# 6moduleboard.net
KiCad netlist of a schematic drawn in EAGLE
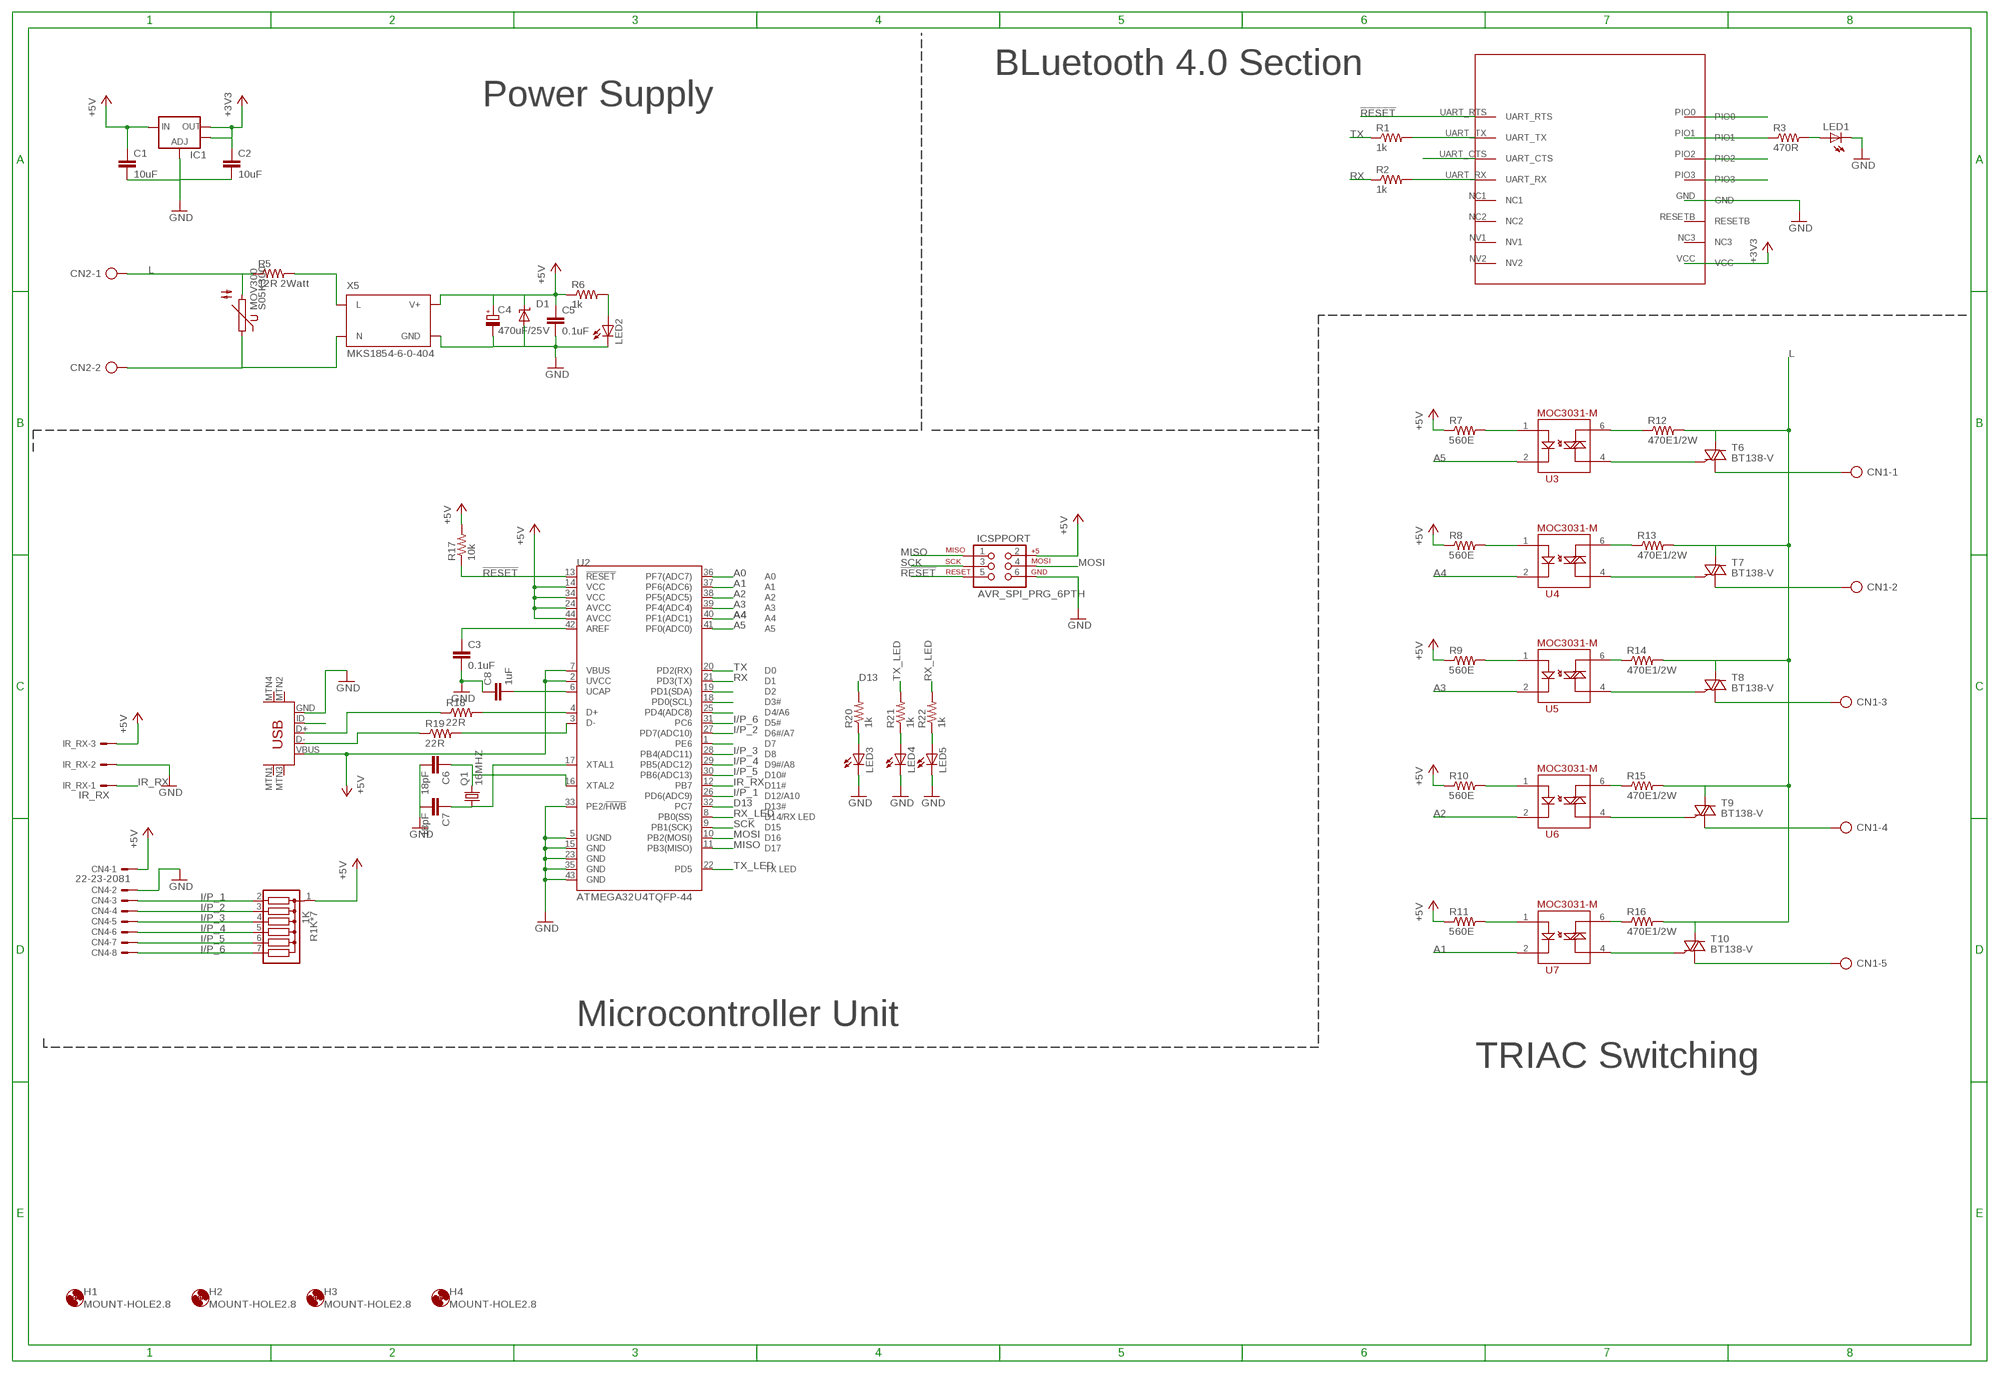
[diagram p0: schematic, sheet 1]

(export (version "E")
  (design (tool "Eeschema 10.0.6"))
  (components
    (comp (ref "C1")
      (value "10uF")
      (footprint "eagle-import:1206")
      (libsource (lib "eagle-import") (part "10UF-6.3V-20%(1206)"))
    )
    (comp (ref "C2")
      (value "10uF")
      (footprint "eagle-import:1206")
      (libsource (lib "eagle-import") (part "10UF-6.3V-20%(1206)"))
    )
    (comp (ref "C3")
      (value "0.1uF")
      (footprint "eagle-import:1206")
      (libsource (lib "eagle-import") (part "CAP1206"))
    )
    (comp (ref "C4")
      (value "470uF/25V")
      (footprint "eagle-import:E5-8,5")
      (libsource (lib "eagle-import") (part "CPOL-EUE5-8.5"))
    )
    (comp (ref "C5")
      (value "0.1uF")
      (footprint "eagle-import:1206")
      (libsource (lib "eagle-import") (part "1.0UF50V10%(1206)"))
    )
    (comp (ref "C6")
      (value "18pF")
      (footprint "eagle-import:1206")
      (libsource (lib "eagle-import") (part "CAP1206"))
    )
    (comp (ref "C7")
      (value "18pF")
      (footprint "eagle-import:1206")
      (libsource (lib "eagle-import") (part "CAP1206"))
    )
    (comp (ref "C8")
      (value "1uF")
      (footprint "eagle-import:1206")
      (libsource (lib "eagle-import") (part "CAP1206"))
    )
    (comp (ref "CN1")
      (value "AK300/5")
      (footprint "eagle-import:AK300_5")
      (libsource (lib "eagle-import") (part "AK300/5"))
    )
    (comp (ref "CN2")
      (value "AK300/2")
      (footprint "eagle-import:AK300_2")
      (libsource (lib "eagle-import") (part "AK300/2"))
    )
    (comp (ref "CN4")
      (value "22-23-2081")
      (footprint "eagle-import:22-23-2081")
      (fields (field (name "MF") "MOLEX"))
      (libsource (lib "eagle-import") (part "22-23-2081"))
    )
    (comp (ref "D1")
      (value "SUPPRESSOR-SMBJ")
      (footprint "eagle-import:SMBJ")
      (libsource (lib "eagle-import") (part "SUPPRESSOR-SMBJ"))
    )
    (comp (ref "H1")
      (value "MOUNT-HOLE2.8")
      (footprint "eagle-import:2,8")
      (libsource (lib "eagle-import") (part "MOUNT-HOLE2.8"))
    )
    (comp (ref "H2")
      (value "MOUNT-HOLE2.8")
      (footprint "eagle-import:2,8")
      (libsource (lib "eagle-import") (part "MOUNT-HOLE2.8"))
    )
    (comp (ref "H3")
      (value "MOUNT-HOLE2.8")
      (footprint "eagle-import:2,8")
      (libsource (lib "eagle-import") (part "MOUNT-HOLE2.8"))
    )
    (comp (ref "H4")
      (value "MOUNT-HOLE2.8")
      (footprint "eagle-import:2,8")
      (libsource (lib "eagle-import") (part "MOUNT-HOLE2.8"))
    )
    (comp (ref "IC1")
      (value "V_REG_LM1117SOT223")
      (footprint "eagle-import:SOT223")
      (libsource (lib "eagle-import") (part "V_REG_LM1117SOT223"))
    )
    (comp (ref "ICSPPORT")
      (value "AVR_SPI_PRG_6PTH")
      (footprint "eagle-import:2X3")
      (libsource (lib "eagle-import") (part "AVR_SPI_PRG_6PTH"))
    )
    (comp (ref "IR_RX")
      (value "IR_RX")
      (footprint "eagle-import:22-23-2031")
      (fields (field (name "MF") "MOLEX") (field (name "MPN") "22-23-2031"))
      (libsource (lib "eagle-import") (part "22-23-2031"))
    )
    (comp (ref "LED1")
      (value "LEDSMT1206")
      (footprint "eagle-import:1206")
      (libsource (lib "eagle-import") (part "LEDSMT1206"))
    )
    (comp (ref "LED2")
      (value "LEDSMT1206")
      (footprint "eagle-import:1206")
      (libsource (lib "eagle-import") (part "LEDSMT1206"))
    )
    (comp (ref "LED3")
      (value "LEDSMT1206")
      (footprint "eagle-import:1206")
      (libsource (lib "eagle-import") (part "LEDSMT1206"))
    )
    (comp (ref "LED4")
      (value "LEDSMT1206")
      (footprint "eagle-import:1206")
      (libsource (lib "eagle-import") (part "LEDSMT1206"))
    )
    (comp (ref "LED5")
      (value "LEDSMT1206")
      (footprint "eagle-import:1206")
      (libsource (lib "eagle-import") (part "LEDSMT1206"))
    )
    (comp (ref "MOV300")
      (value "S05K300")
      (footprint "eagle-import:S05K300")
      (libsource (lib "eagle-import") (part "S05K300"))
    )
    (comp (ref "Q1")
      (value "16MHZ")
      (footprint "eagle-import:HC49UP")
      (libsource (lib "eagle-import") (part "CRYSTALHC49UP"))
    )
    (comp (ref "R1")
      (value "1k")
      (footprint "eagle-import:1206")
      (libsource (lib "eagle-import") (part "RESISTOR1206"))
    )
    (comp (ref "R1K*7")
      (value "1K")
      (footprint "eagle-import:SIL7")
      (libsource (lib "eagle-import") (part "G06R"))
    )
    (comp (ref "R2")
      (value "1k")
      (footprint "eagle-import:1206")
      (libsource (lib "eagle-import") (part "RESISTOR1206"))
    )
    (comp (ref "R3")
      (value "470R")
      (footprint "eagle-import:1206")
      (libsource (lib "eagle-import") (part "RESISTOR1206"))
    )
    (comp (ref "R5")
      (value "12R 2Watt")
      (footprint "eagle-import:0207_10")
      (libsource (lib "eagle-import") (part "R-US_0207/10"))
    )
    (comp (ref "R6")
      (value "1k")
      (footprint "eagle-import:1206")
      (libsource (lib "eagle-import") (part "RESISTOR1206"))
    )
    (comp (ref "R7")
      (value "560E")
      (footprint "eagle-import:1206")
      (libsource (lib "eagle-import") (part "SparkFun-Resistors_RESISTOR1206"))
    )
    (comp (ref "R8")
      (value "560E")
      (footprint "eagle-import:1206")
      (libsource (lib "eagle-import") (part "SparkFun-Resistors_RESISTOR1206"))
    )
    (comp (ref "R9")
      (value "560E")
      (footprint "eagle-import:1206")
      (libsource (lib "eagle-import") (part "SparkFun-Resistors_RESISTOR1206"))
    )
    (comp (ref "R10")
      (value "560E")
      (footprint "eagle-import:1206")
      (libsource (lib "eagle-import") (part "SparkFun-Resistors_RESISTOR1206"))
    )
    (comp (ref "R11")
      (value "560E")
      (footprint "eagle-import:1206")
      (libsource (lib "eagle-import") (part "SparkFun-Resistors_RESISTOR1206"))
    )
    (comp (ref "R12")
      (value "470E1/2W")
      (footprint "eagle-import:0411V")
      (libsource (lib "eagle-import") (part "R-US_0411/3V"))
    )
    (comp (ref "R13")
      (value "470E1/2W")
      (footprint "eagle-import:0411V")
      (libsource (lib "eagle-import") (part "R-US_0411/3V"))
    )
    (comp (ref "R14")
      (value "470E1/2W")
      (footprint "eagle-import:0411V")
      (libsource (lib "eagle-import") (part "R-US_0411/3V"))
    )
    (comp (ref "R15")
      (value "470E1/2W")
      (footprint "eagle-import:0411V")
      (libsource (lib "eagle-import") (part "R-US_0411/3V"))
    )
    (comp (ref "R16")
      (value "470E1/2W")
      (footprint "eagle-import:0411V")
      (libsource (lib "eagle-import") (part "R-US_0411/3V"))
    )
    (comp (ref "R17")
      (value "10k")
      (footprint "eagle-import:1206")
      (libsource (lib "eagle-import") (part "RESISTOR1206"))
    )
    (comp (ref "R18")
      (value "22R")
      (footprint "eagle-import:1206")
      (libsource (lib "eagle-import") (part "RESISTOR1206"))
    )
    (comp (ref "R19")
      (value "22R")
      (footprint "eagle-import:1206")
      (libsource (lib "eagle-import") (part "RESISTOR1206"))
    )
    (comp (ref "R20")
      (value "1k")
      (footprint "eagle-import:1206")
      (libsource (lib "eagle-import") (part "RESISTOR1206"))
    )
    (comp (ref "R21")
      (value "1k")
      (footprint "eagle-import:1206")
      (libsource (lib "eagle-import") (part "RESISTOR1206"))
    )
    (comp (ref "R22")
      (value "1k")
      (footprint "eagle-import:1206")
      (libsource (lib "eagle-import") (part "RESISTOR1206"))
    )
    (comp (ref "T6")
      (value "BT138-V")
      (footprint "eagle-import:TO220BV")
      (libsource (lib "eagle-import") (part "BT138-V"))
    )
    (comp (ref "T7")
      (value "BT138-V")
      (footprint "eagle-import:TO220BV")
      (libsource (lib "eagle-import") (part "BT138-V"))
    )
    (comp (ref "T8")
      (value "BT138-V")
      (footprint "eagle-import:TO220BV")
      (libsource (lib "eagle-import") (part "BT138-V"))
    )
    (comp (ref "T9")
      (value "BT138-V")
      (footprint "eagle-import:TO220BV")
      (libsource (lib "eagle-import") (part "BT138-V"))
    )
    (comp (ref "T10")
      (value "BT138-V")
      (footprint "eagle-import:TO220BV")
      (libsource (lib "eagle-import") (part "BT138-V"))
    )
    (comp (ref "U$1")
      (value "HM-11")
      (footprint "eagle-import:HM-11")
      (libsource (lib "eagle-import") (part "HM-11"))
    )
    (comp (ref "U2")
      (value "ATMEGA32U4TQFP-44")
      (footprint "eagle-import:TQFP44")
      (libsource (lib "eagle-import") (part "ATMEGA32U4TQFP-44"))
    )
    (comp (ref "U3")
      (value "MOC3083")
      (footprint "eagle-import:DIL06")
      (libsource (lib "eagle-import") (part "MOC3031-M"))
    )
    (comp (ref "U4")
      (value "MOC3083")
      (footprint "eagle-import:DIL06")
      (libsource (lib "eagle-import") (part "MOC3031-M"))
    )
    (comp (ref "U5")
      (value "MOC3083")
      (footprint "eagle-import:DIL06")
      (libsource (lib "eagle-import") (part "MOC3031-M"))
    )
    (comp (ref "U6")
      (value "MOC3083")
      (footprint "eagle-import:DIL06")
      (libsource (lib "eagle-import") (part "MOC3031-M"))
    )
    (comp (ref "U7")
      (value "MOC3083")
      (footprint "eagle-import:DIL06")
      (libsource (lib "eagle-import") (part "MOC3031-M"))
    )
    (comp (ref "U8")
      (value "USB-MINIB-5PIN")
      (footprint "eagle-import:USB-MINIB")
      (libsource (lib "eagle-import") (part "USB-MINIB-5PIN"))
    )
    (comp (ref "X5")
      (value "MKS1854-6-0-404")
      (footprint "eagle-import:MKS1854-6-0-404")
      (libsource (lib "eagle-import") (part "MKS1854-6-0-404"))
    )
  )
  (nets
    (net (code "1") (name "+3V3") (class "Default")
      (node (ref "C2") (pin "1") (pinfunction "1_1") (pintype "passive"))
      (node (ref "IC1") (pin "2") (pinfunction "OUT_2") (pintype "output"))
      (node (ref "IC1") (pin "4") (pinfunction "OUT_4") (pintype "output"))
      (node (ref "U$1") (pin "VCC") (pinfunction "VCC_VCC") (pintype "bidirectional"))
    )
    (net (code "2") (name "+5V") (class "Default")
      (node (ref "C1") (pin "1") (pinfunction "1_1") (pintype "passive"))
      (node (ref "C4") (pin "+") (pinfunction "+_+") (pintype "passive"))
      (node (ref "C5") (pin "1") (pinfunction "1_1") (pintype "passive"))
      (node (ref "CN4") (pin "1") (pinfunction "S_1") (pintype "passive"))
      (node (ref "D1") (pin "C") (pinfunction "C_C") (pintype "passive"))
      (node (ref "IC1") (pin "3") (pinfunction "IN_3") (pintype "input"))
      (node (ref "ICSPPORT") (pin "2") (pinfunction "2_2") (pintype "passive"))
      (node (ref "IR_RX") (pin "3") (pinfunction "S_3") (pintype "passive"))
      (node (ref "R10") (pin "1") (pinfunction "1_1") (pintype "passive"))
      (node (ref "R11") (pin "1") (pinfunction "1_1") (pintype "passive"))
      (node (ref "R17") (pin "2") (pinfunction "2_2") (pintype "passive"))
      (node (ref "R1K*7") (pin "1") (pinfunction "1_1") (pintype "passive"))
      (node (ref "R6") (pin "1") (pinfunction "1_1") (pintype "passive"))
      (node (ref "R7") (pin "1") (pinfunction "1_1") (pintype "passive"))
      (node (ref "R8") (pin "1") (pinfunction "1_1") (pintype "passive"))
      (node (ref "R9") (pin "1") (pinfunction "1_1") (pintype "passive"))
      (node (ref "U2") (pin "14") (pinfunction "VCC_14") (pintype "bidirectional"))
      (node (ref "U2") (pin "2") (pinfunction "UVCC_2") (pintype "bidirectional"))
      (node (ref "U2") (pin "24") (pinfunction "AVCC_24") (pintype "bidirectional"))
      (node (ref "U2") (pin "34") (pinfunction "VCC_34") (pintype "bidirectional"))
      (node (ref "U2") (pin "44") (pinfunction "AVCC_44") (pintype "bidirectional"))
      (node (ref "U2") (pin "7") (pinfunction "VBUS_7") (pintype "bidirectional"))
      (node (ref "U8") (pin "VBUS") (pinfunction "VBUS_VBUS") (pintype "bidirectional"))
      (node (ref "X5") (pin "3") (pinfunction "V+_3") (pintype "input"))
    )
    (net (code "3") (name "/A0") (class "Default")
      (node (ref "U2") (pin "36") (pinfunction "PF7(ADC7)_36") (pintype "bidirectional"))
    )
    (net (code "4") (name "/A1") (class "Default")
      (node (ref "U2") (pin "37") (pinfunction "PF6(ADC6)_37") (pintype "bidirectional"))
      (node (ref "U7") (pin "2") (pinfunction "2_2") (pintype "bidirectional"))
    )
    (net (code "5") (name "/A2") (class "Default")
      (node (ref "U2") (pin "38") (pinfunction "PF5(ADC5)_38") (pintype "bidirectional"))
      (node (ref "U6") (pin "2") (pinfunction "2_2") (pintype "bidirectional"))
    )
    (net (code "6") (name "/A3") (class "Default")
      (node (ref "U2") (pin "39") (pinfunction "PF4(ADC4)_39") (pintype "bidirectional"))
      (node (ref "U5") (pin "2") (pinfunction "2_2") (pintype "bidirectional"))
    )
    (net (code "7") (name "/A4") (class "Default")
      (node (ref "U2") (pin "40") (pinfunction "PF1(ADC1)_40") (pintype "bidirectional"))
      (node (ref "U4") (pin "2") (pinfunction "2_2") (pintype "bidirectional"))
    )
    (net (code "8") (name "/A5") (class "Default")
      (node (ref "U2") (pin "41") (pinfunction "PF0(ADC0)_41") (pintype "bidirectional"))
      (node (ref "U3") (pin "2") (pinfunction "2_2") (pintype "bidirectional"))
    )
    (net (code "9") (name "/D13") (class "Default")
      (node (ref "R20") (pin "2") (pinfunction "2_2") (pintype "passive"))
      (node (ref "U2") (pin "32") (pinfunction "PC7_32") (pintype "bidirectional"))
    )
    (net (code "10") (name "/IR_RX") (class "Default")
      (node (ref "IR_RX") (pin "1") (pinfunction "S_1") (pintype "passive"))
      (node (ref "U2") (pin "12") (pinfunction "PB7_12") (pintype "bidirectional"))
    )
    (net (code "11") (name "/I{slash}P_1") (class "Default")
      (node (ref "CN4") (pin "3") (pinfunction "S_3") (pintype "passive"))
      (node (ref "R1K*7") (pin "2") (pinfunction "2_2") (pintype "passive"))
      (node (ref "U2") (pin "26") (pinfunction "PD6(ADC9)_26") (pintype "bidirectional"))
    )
    (net (code "12") (name "/I{slash}P_2") (class "Default")
      (node (ref "CN4") (pin "4") (pinfunction "S_4") (pintype "passive"))
      (node (ref "R1K*7") (pin "3") (pinfunction "3_3") (pintype "passive"))
      (node (ref "U2") (pin "27") (pinfunction "PD7(ADC10)_27") (pintype "bidirectional"))
    )
    (net (code "13") (name "/I{slash}P_3") (class "Default")
      (node (ref "CN4") (pin "5") (pinfunction "S_5") (pintype "passive"))
      (node (ref "R1K*7") (pin "4") (pinfunction "4_4") (pintype "passive"))
      (node (ref "U2") (pin "28") (pinfunction "PB4(ADC11)_28") (pintype "bidirectional"))
    )
    (net (code "14") (name "/I{slash}P_4") (class "Default")
      (node (ref "CN4") (pin "6") (pinfunction "S_6") (pintype "passive"))
      (node (ref "R1K*7") (pin "5") (pinfunction "5_5") (pintype "passive"))
      (node (ref "U2") (pin "29") (pinfunction "PB5(ADC12)_29") (pintype "bidirectional"))
    )
    (net (code "15") (name "/I{slash}P_5") (class "Default")
      (node (ref "CN4") (pin "7") (pinfunction "S_7") (pintype "passive"))
      (node (ref "R1K*7") (pin "6") (pinfunction "6_6") (pintype "passive"))
      (node (ref "U2") (pin "30") (pinfunction "PB6(ADC13)_30") (pintype "bidirectional"))
    )
    (net (code "16") (name "/I{slash}P_6") (class "Default")
      (node (ref "CN4") (pin "8") (pinfunction "S_8") (pintype "passive"))
      (node (ref "R1K*7") (pin "7") (pinfunction "7_7") (pintype "passive"))
      (node (ref "U2") (pin "31") (pinfunction "PC6_31") (pintype "bidirectional"))
    )
    (net (code "17") (name "/L") (class "Default")
      (node (ref "CN2") (pin "1") (pinfunction "KL_1") (pintype "passive"))
      (node (ref "MOV300") (pin "2") (pinfunction "2_2") (pintype "passive"))
      (node (ref "R12") (pin "2") (pinfunction "2_2") (pintype "passive"))
      (node (ref "R13") (pin "2") (pinfunction "2_2") (pintype "passive"))
      (node (ref "R14") (pin "2") (pinfunction "2_2") (pintype "passive"))
      (node (ref "R15") (pin "2") (pinfunction "2_2") (pintype "passive"))
      (node (ref "R16") (pin "2") (pinfunction "2_2") (pintype "passive"))
      (node (ref "R5") (pin "1") (pinfunction "1_1") (pintype "passive"))
      (node (ref "T10") (pin "T2") (pinfunction "A2_T2") (pintype "passive"))
      (node (ref "T6") (pin "T2") (pinfunction "A2_T2") (pintype "passive"))
      (node (ref "T7") (pin "T2") (pinfunction "A2_T2") (pintype "passive"))
      (node (ref "T8") (pin "T2") (pinfunction "A2_T2") (pintype "passive"))
      (node (ref "T9") (pin "T2") (pinfunction "A2_T2") (pintype "passive"))
    )
    (net (code "18") (name "/MISO") (class "Default")
      (node (ref "ICSPPORT") (pin "1") (pinfunction "1_1") (pintype "passive"))
      (node (ref "U2") (pin "11") (pinfunction "PB3(MISO)_11") (pintype "bidirectional"))
    )
    (net (code "19") (name "/MOSI") (class "Default")
      (node (ref "ICSPPORT") (pin "4") (pinfunction "4_4") (pintype "passive"))
      (node (ref "U2") (pin "10") (pinfunction "PB2(MOSI)_10") (pintype "bidirectional"))
    )
    (net (code "20") (name "/RX") (class "Default")
      (node (ref "R2") (pin "1") (pinfunction "1_1") (pintype "passive"))
      (node (ref "U2") (pin "21") (pinfunction "PD3(TX)_21") (pintype "bidirectional"))
    )
    (net (code "21") (name "/RX_LED") (class "Default")
      (node (ref "R22") (pin "2") (pinfunction "2_2") (pintype "passive"))
      (node (ref "U2") (pin "8") (pinfunction "PB0(SS)_8") (pintype "bidirectional"))
    )
    (net (code "22") (name "/SCK") (class "Default")
      (node (ref "ICSPPORT") (pin "3") (pinfunction "3_3") (pintype "passive"))
      (node (ref "U2") (pin "9") (pinfunction "PB1(SCK)_9") (pintype "bidirectional"))
    )
    (net (code "23") (name "/TX") (class "Default")
      (node (ref "R1") (pin "1") (pinfunction "1_1") (pintype "passive"))
      (node (ref "U2") (pin "20") (pinfunction "PD2(RX)_20") (pintype "bidirectional"))
    )
    (net (code "24") (name "/TX_LED") (class "Default")
      (node (ref "R21") (pin "2") (pinfunction "2_2") (pintype "passive"))
      (node (ref "U2") (pin "22") (pinfunction "PD5_22") (pintype "bidirectional"))
    )
    (net (code "25") (name "/~{RESET}") (class "Default")
      (node (ref "ICSPPORT") (pin "5") (pinfunction "5_5") (pintype "passive"))
      (node (ref "R17") (pin "1") (pinfunction "1_1") (pintype "passive"))
      (node (ref "U$1") (pin "UART_RTS") (pinfunction "UART_RTS_UART_RTS") (pintype "bidirectional"))
      (node (ref "U2") (pin "13") (pinfunction "~{RESET}_13") (pintype "bidirectional"))
    )
    (net (code "26") (name "GND") (class "Default")
      (node (ref "C1") (pin "2") (pinfunction "2_2") (pintype "passive"))
      (node (ref "C2") (pin "2") (pinfunction "2_2") (pintype "passive"))
      (node (ref "C3") (pin "2") (pinfunction "2_2") (pintype "passive"))
      (node (ref "C4") (pin "-") (pinfunction "-_-") (pintype "passive"))
      (node (ref "C5") (pin "2") (pinfunction "2_2") (pintype "passive"))
      (node (ref "C6") (pin "2") (pinfunction "2_2") (pintype "passive"))
      (node (ref "C7") (pin "2") (pinfunction "2_2") (pintype "passive"))
      (node (ref "C8") (pin "1") (pinfunction "1_1") (pintype "passive"))
      (node (ref "CN4") (pin "2") (pinfunction "S_2") (pintype "passive"))
      (node (ref "D1") (pin "A") (pinfunction "A_A") (pintype "passive"))
      (node (ref "IC1") (pin "1") (pinfunction "ADJ_1") (pintype "input"))
      (node (ref "ICSPPORT") (pin "6") (pinfunction "6_6") (pintype "passive"))
      (node (ref "IR_RX") (pin "2") (pinfunction "S_2") (pintype "passive"))
      (node (ref "LED1") (pin "C") (pinfunction "C_C") (pintype "passive"))
      (node (ref "LED2") (pin "C") (pinfunction "C_C") (pintype "passive"))
      (node (ref "LED3") (pin "C") (pinfunction "C_C") (pintype "passive"))
      (node (ref "LED4") (pin "C") (pinfunction "C_C") (pintype "passive"))
      (node (ref "LED5") (pin "C") (pinfunction "C_C") (pintype "passive"))
      (node (ref "U$1") (pin "GND") (pinfunction "GND_GND") (pintype "bidirectional"))
      (node (ref "U2") (pin "15") (pinfunction "GND_15") (pintype "bidirectional"))
      (node (ref "U2") (pin "23") (pinfunction "GND_23") (pintype "bidirectional"))
      (node (ref "U2") (pin "33") (pinfunction "PE2/~{HWB}_33") (pintype "bidirectional"))
      (node (ref "U2") (pin "35") (pinfunction "GND_35") (pintype "bidirectional"))
      (node (ref "U2") (pin "43") (pinfunction "GND_43") (pintype "bidirectional"))
      (node (ref "U2") (pin "5") (pinfunction "UGND_5") (pintype "bidirectional"))
      (node (ref "U8") (pin "GND") (pinfunction "GND_GND") (pintype "bidirectional"))
      (node (ref "X5") (pin "4") (pinfunction "GND_4") (pintype "input"))
    )
    (net (code "27") (name "Net-(CN1A-KL)") (class "Default")
      (node (ref "CN1") (pin "1") (pinfunction "KL_1") (pintype "passive"))
      (node (ref "T6") (pin "T1") (pinfunction "A1_T1") (pintype "passive"))
    )
    (net (code "28") (name "Net-(CN1B-KL)") (class "Default")
      (node (ref "CN1") (pin "2") (pinfunction "KL_2") (pintype "passive"))
      (node (ref "T7") (pin "T1") (pinfunction "A1_T1") (pintype "passive"))
    )
    (net (code "29") (name "Net-(CN1C-KL)") (class "Default")
      (node (ref "CN1") (pin "3") (pinfunction "KL_3") (pintype "passive"))
      (node (ref "T8") (pin "T1") (pinfunction "A1_T1") (pintype "passive"))
    )
    (net (code "30") (name "Net-(CN1D-KL)") (class "Default")
      (node (ref "CN1") (pin "4") (pinfunction "KL_4") (pintype "passive"))
      (node (ref "T9") (pin "T1") (pinfunction "A1_T1") (pintype "passive"))
    )
    (net (code "31") (name "Net-(CN1E-KL)") (class "Default")
      (node (ref "CN1") (pin "5") (pinfunction "KL_5") (pintype "passive"))
      (node (ref "T10") (pin "T1") (pinfunction "A1_T1") (pintype "passive"))
    )
    (net (code "32") (name "Net-(CN2B-KL)") (class "Default")
      (node (ref "CN2") (pin "2") (pinfunction "KL_2") (pintype "passive"))
      (node (ref "MOV300") (pin "1") (pinfunction "1_1") (pintype "passive"))
      (node (ref "X5") (pin "2") (pinfunction "N_2") (pintype "input"))
    )
    (net (code "33") (name "Net-(LED1-PadA)") (class "Default")
      (node (ref "LED1") (pin "A") (pinfunction "A_A") (pintype "passive"))
      (node (ref "R3") (pin "2") (pinfunction "2_2") (pintype "passive"))
    )
    (net (code "34") (name "Net-(LED2-PadA)") (class "Default")
      (node (ref "LED2") (pin "A") (pinfunction "A_A") (pintype "passive"))
      (node (ref "R6") (pin "2") (pinfunction "2_2") (pintype "passive"))
    )
    (net (code "35") (name "Net-(LED3-PadA)") (class "Default")
      (node (ref "LED3") (pin "A") (pinfunction "A_A") (pintype "passive"))
      (node (ref "R20") (pin "1") (pinfunction "1_1") (pintype "passive"))
    )
    (net (code "36") (name "Net-(LED4-PadA)") (class "Default")
      (node (ref "LED4") (pin "A") (pinfunction "A_A") (pintype "passive"))
      (node (ref "R21") (pin "1") (pinfunction "1_1") (pintype "passive"))
    )
    (net (code "37") (name "Net-(LED5-PadA)") (class "Default")
      (node (ref "LED5") (pin "A") (pinfunction "A_A") (pintype "passive"))
      (node (ref "R22") (pin "1") (pinfunction "1_1") (pintype "passive"))
    )
    (net (code "38") (name "Net-(R1-Pad2)") (class "Default")
      (node (ref "R1") (pin "2") (pinfunction "2_2") (pintype "passive"))
      (node (ref "U$1") (pin "UART_TX") (pinfunction "UART_TX_UART_TX") (pintype "bidirectional"))
    )
    (net (code "39") (name "Net-(R2-Pad2)") (class "Default")
      (node (ref "R2") (pin "2") (pinfunction "2_2") (pintype "passive"))
      (node (ref "U$1") (pin "UART_RX") (pinfunction "UART_RX_UART_RX") (pintype "bidirectional"))
    )
    (net (code "40") (name "Net-(R3-Pad1)") (class "Default")
      (node (ref "R3") (pin "1") (pinfunction "1_1") (pintype "passive"))
      (node (ref "U$1") (pin "PIO1") (pinfunction "PIO1_PIO1") (pintype "bidirectional"))
    )
    (net (code "41") (name "Net-(R7-Pad2)") (class "Default")
      (node (ref "R7") (pin "2") (pinfunction "2_2") (pintype "passive"))
      (node (ref "U3") (pin "1") (pinfunction "1_1") (pintype "bidirectional"))
    )
    (net (code "42") (name "Net-(R8-Pad2)") (class "Default")
      (node (ref "R8") (pin "2") (pinfunction "2_2") (pintype "passive"))
      (node (ref "U4") (pin "1") (pinfunction "1_1") (pintype "bidirectional"))
    )
    (net (code "43") (name "Net-(R9-Pad2)") (class "Default")
      (node (ref "R9") (pin "2") (pinfunction "2_2") (pintype "passive"))
      (node (ref "U5") (pin "1") (pinfunction "1_1") (pintype "bidirectional"))
    )
    (net (code "44") (name "Net-(R10-Pad2)") (class "Default")
      (node (ref "R10") (pin "2") (pinfunction "2_2") (pintype "passive"))
      (node (ref "U6") (pin "1") (pinfunction "1_1") (pintype "bidirectional"))
    )
    (net (code "45") (name "Net-(R11-Pad2)") (class "Default")
      (node (ref "R11") (pin "2") (pinfunction "2_2") (pintype "passive"))
      (node (ref "U7") (pin "1") (pinfunction "1_1") (pintype "bidirectional"))
    )
    (net (code "46") (name "Net-(R12-Pad1)") (class "Default")
      (node (ref "R12") (pin "1") (pinfunction "1_1") (pintype "passive"))
      (node (ref "U3") (pin "6") (pinfunction "6_6") (pintype "bidirectional"))
    )
    (net (code "47") (name "Net-(R13-Pad1)") (class "Default")
      (node (ref "R13") (pin "1") (pinfunction "1_1") (pintype "passive"))
      (node (ref "U4") (pin "6") (pinfunction "6_6") (pintype "bidirectional"))
    )
    (net (code "48") (name "Net-(R14-Pad1)") (class "Default")
      (node (ref "R14") (pin "1") (pinfunction "1_1") (pintype "passive"))
      (node (ref "U5") (pin "6") (pinfunction "6_6") (pintype "bidirectional"))
    )
    (net (code "49") (name "Net-(R15-Pad1)") (class "Default")
      (node (ref "R15") (pin "1") (pinfunction "1_1") (pintype "passive"))
      (node (ref "U6") (pin "6") (pinfunction "6_6") (pintype "bidirectional"))
    )
    (net (code "50") (name "Net-(R16-Pad1)") (class "Default")
      (node (ref "R16") (pin "1") (pinfunction "1_1") (pintype "passive"))
      (node (ref "U7") (pin "6") (pinfunction "6_6") (pintype "bidirectional"))
    )
    (net (code "51") (name "Net-(R18-Pad1)") (class "Default")
      (node (ref "R18") (pin "1") (pinfunction "1_1") (pintype "passive"))
      (node (ref "U8") (pin "D+") (pinfunction "D+_D+") (pintype "bidirectional"))
    )
    (net (code "52") (name "Net-(R19-Pad1)") (class "Default")
      (node (ref "R19") (pin "1") (pinfunction "1_1") (pintype "passive"))
      (node (ref "U8") (pin "D-") (pinfunction "D-_D-") (pintype "bidirectional"))
    )
    (net (code "53") (name "Net-(T6-PadG)") (class "Default")
      (node (ref "T6") (pin "G") (pinfunction "G_G") (pintype "passive"))
      (node (ref "U3") (pin "4") (pinfunction "4_4") (pintype "bidirectional"))
    )
    (net (code "54") (name "Net-(T7-PadG)") (class "Default")
      (node (ref "T7") (pin "G") (pinfunction "G_G") (pintype "passive"))
      (node (ref "U4") (pin "4") (pinfunction "4_4") (pintype "bidirectional"))
    )
    (net (code "55") (name "Net-(T8-PadG)") (class "Default")
      (node (ref "T8") (pin "G") (pinfunction "G_G") (pintype "passive"))
      (node (ref "U5") (pin "4") (pinfunction "4_4") (pintype "bidirectional"))
    )
    (net (code "56") (name "Net-(T9-PadG)") (class "Default")
      (node (ref "T9") (pin "G") (pinfunction "G_G") (pintype "passive"))
      (node (ref "U6") (pin "4") (pinfunction "4_4") (pintype "bidirectional"))
    )
    (net (code "57") (name "Net-(T10-PadG)") (class "Default")
      (node (ref "T10") (pin "G") (pinfunction "G_G") (pintype "passive"))
      (node (ref "U7") (pin "4") (pinfunction "4_4") (pintype "bidirectional"))
    )
    (net (code "58") (name "Net-(U2-AREF)") (class "Default")
      (node (ref "C3") (pin "1") (pinfunction "1_1") (pintype "passive"))
      (node (ref "U2") (pin "42") (pinfunction "AREF_42") (pintype "bidirectional"))
    )
    (net (code "59") (name "Net-(U2-D+)") (class "Default")
      (node (ref "R18") (pin "2") (pinfunction "2_2") (pintype "passive"))
      (node (ref "U2") (pin "4") (pinfunction "D+_4") (pintype "bidirectional"))
    )
    (net (code "60") (name "Net-(U2-D-)") (class "Default")
      (node (ref "R19") (pin "2") (pinfunction "2_2") (pintype "passive"))
      (node (ref "U2") (pin "3") (pinfunction "D-_3") (pintype "bidirectional"))
    )
    (net (code "61") (name "Net-(U2-UCAP)") (class "Default")
      (node (ref "C8") (pin "2") (pinfunction "2_2") (pintype "passive"))
      (node (ref "U2") (pin "6") (pinfunction "UCAP_6") (pintype "bidirectional"))
    )
    (net (code "62") (name "Net-(U2-XTAL1)") (class "Default")
      (node (ref "C7") (pin "1") (pinfunction "1_1") (pintype "passive"))
      (node (ref "Q1") (pin "1") (pinfunction "1_1") (pintype "passive"))
      (node (ref "U2") (pin "17") (pinfunction "XTAL1_17") (pintype "bidirectional"))
    )
    (net (code "63") (name "Net-(U2-XTAL2)") (class "Default")
      (node (ref "C6") (pin "1") (pinfunction "1_1") (pintype "passive"))
      (node (ref "Q1") (pin "2") (pinfunction "2_2") (pintype "passive"))
      (node (ref "U2") (pin "16") (pinfunction "XTAL2_16") (pintype "bidirectional"))
    )
    (net (code "64") (name "Net-(X5-L)") (class "Default")
      (node (ref "R5") (pin "2") (pinfunction "2_2") (pintype "passive"))
      (node (ref "X5") (pin "1") (pinfunction "L_1") (pintype "input"))
    )
    (net (code "65") (name "unconnected-(U$1-PadNC1)") (class "Default")
      (node (ref "U$1") (pin "NC1") (pinfunction "NC1_NC1") (pintype "bidirectional"))
    )
    (net (code "66") (name "unconnected-(U$1-PadNC2)") (class "Default")
      (node (ref "U$1") (pin "NC2") (pinfunction "NC2_NC2") (pintype "bidirectional"))
    )
    (net (code "67") (name "unconnected-(U$1-PadNC3)") (class "Default")
      (node (ref "U$1") (pin "NC3") (pinfunction "NC3_NC3") (pintype "bidirectional"))
    )
    (net (code "68") (name "unconnected-(U$1-PadNV1)") (class "Default")
      (node (ref "U$1") (pin "NV1") (pinfunction "NV1_NV1") (pintype "bidirectional"))
    )
    (net (code "69") (name "unconnected-(U$1-PadNV2)") (class "Default")
      (node (ref "U$1") (pin "NV2") (pinfunction "NV2_NV2") (pintype "bidirectional"))
    )
    (net (code "70") (name "unconnected-(U$1-PadPIO0)") (class "Default")
      (node (ref "U$1") (pin "PIO0") (pinfunction "PIO0_PIO0") (pintype "bidirectional"))
    )
    (net (code "71") (name "unconnected-(U$1-PadPIO2)") (class "Default")
      (node (ref "U$1") (pin "PIO2") (pinfunction "PIO2_PIO2") (pintype "bidirectional"))
    )
    (net (code "72") (name "unconnected-(U$1-PadPIO3)") (class "Default")
      (node (ref "U$1") (pin "PIO3") (pinfunction "PIO3_PIO3") (pintype "bidirectional"))
    )
    (net (code "73") (name "unconnected-(U$1-PadRESETB)") (class "Default")
      (node (ref "U$1") (pin "RESETB") (pinfunction "RESETB_RESETB") (pintype "bidirectional"))
    )
    (net (code "74") (name "unconnected-(U$1-PadUART_CTS)") (class "Default")
      (node (ref "U$1") (pin "UART_CTS") (pinfunction "UART_CTS_UART_CTS") (pintype "bidirectional"))
    )
    (net (code "75") (name "unconnected-(U2-PD0(SCL)-Pad18)") (class "Default")
      (node (ref "U2") (pin "18") (pinfunction "PD0(SCL)_18") (pintype "bidirectional"))
    )
    (net (code "76") (name "unconnected-(U2-PD1(SDA)-Pad19)") (class "Default")
      (node (ref "U2") (pin "19") (pinfunction "PD1(SDA)_19") (pintype "bidirectional"))
    )
    (net (code "77") (name "unconnected-(U2-PD4(ADC8)-Pad25)") (class "Default")
      (node (ref "U2") (pin "25") (pinfunction "PD4(ADC8)_25") (pintype "bidirectional"))
    )
    (net (code "78") (name "unconnected-(U2-PE6-Pad1)") (class "Default")
      (node (ref "U2") (pin "1") (pinfunction "PE6_1") (pintype "bidirectional"))
    )
    (net (code "79") (name "unconnected-(U8-MTN1-PadMTN3)") (class "Default")
      (node (ref "U8") (pin "MTN3") (pinfunction "MTN1_MTN3") (pintype "bidirectional"))
    )
    (net (code "80") (name "unconnected-(U8-MTN2-PadMTN1)") (class "Default")
      (node (ref "U8") (pin "MTN1") (pinfunction "MTN2_MTN1") (pintype "bidirectional"))
    )
    (net (code "81") (name "unconnected-(U8-MTN3-PadMTN2)") (class "Default")
      (node (ref "U8") (pin "MTN2") (pinfunction "MTN3_MTN2") (pintype "bidirectional"))
    )
    (net (code "82") (name "unconnected-(U8-PadID)") (class "Default")
      (node (ref "U8") (pin "ID") (pinfunction "ID_ID") (pintype "bidirectional"))
    )
    (net (code "83") (name "unconnected-(U8-PadMTN4)") (class "Default")
      (node (ref "U8") (pin "MTN4") (pinfunction "MTN4_MTN4") (pintype "bidirectional"))
    )
  )
)
